# W681X.net
KiCad netlist of a schematic drawn in EAGLE
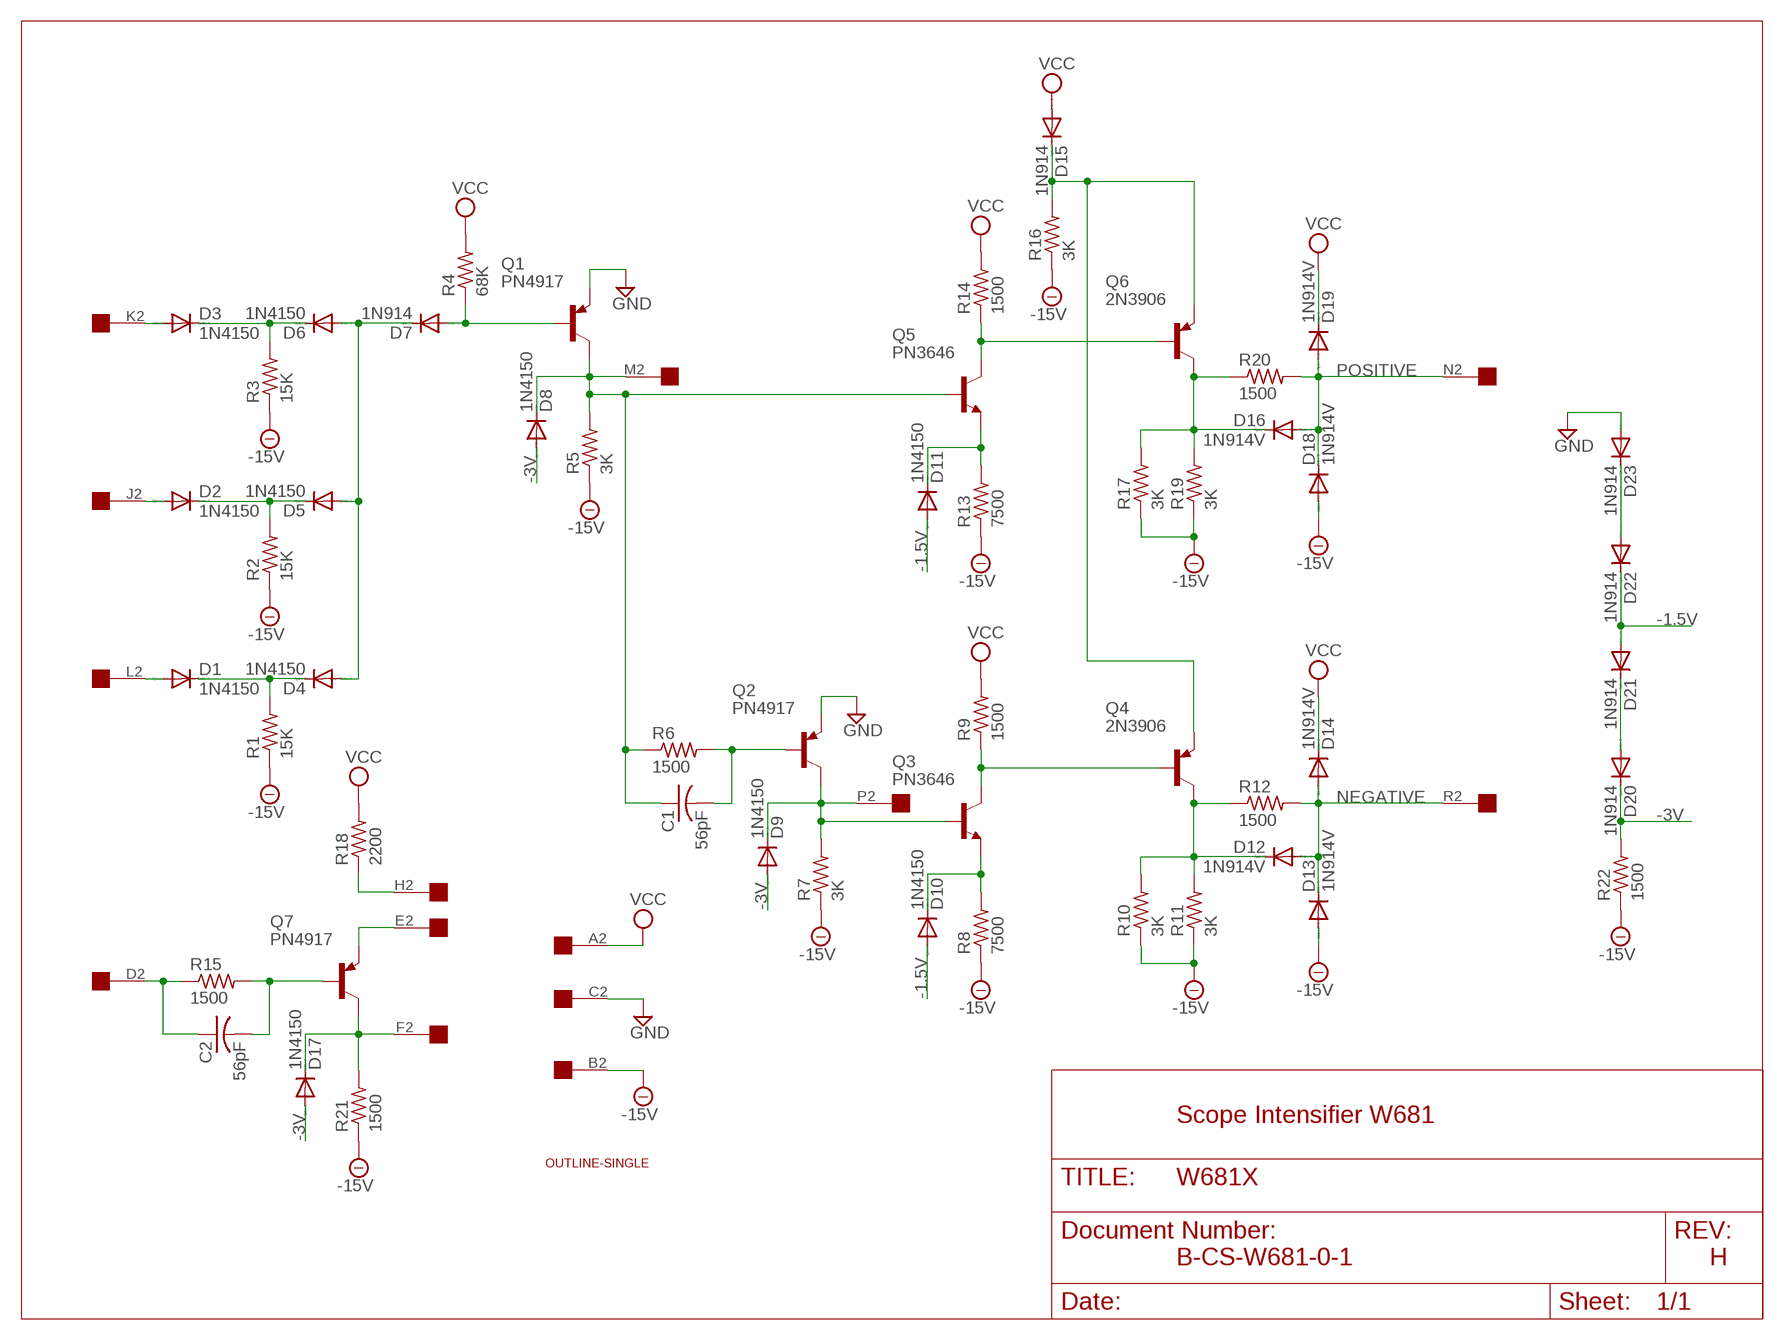
[diagram p0: schematic, sheet 1]

(export (version "E")
  (design (tool "Eeschema 10.0.6"))
  (components
    (comp (ref "C1")
      (value "56pF")
      (footprint "eagle-import:C063-025X075")
      (libsource (lib "eagle-import") (part "C-US"))
    )
    (comp (ref "C2")
      (value "56pF")
      (footprint "eagle-import:C063-025X075")
      (libsource (lib "eagle-import") (part "C-US"))
    )
    (comp (ref "D1")
      (value "1N4150")
      (footprint "eagle-import:DO35-10")
      (libsource (lib "eagle-import") (part "DIODE-DO35-10"))
    )
    (comp (ref "D2")
      (value "1N4150")
      (footprint "eagle-import:DO35-10")
      (libsource (lib "eagle-import") (part "DIODE-DO35-10"))
    )
    (comp (ref "D3")
      (value "1N4150")
      (footprint "eagle-import:DO35-10")
      (libsource (lib "eagle-import") (part "DIODE-DO35-10"))
    )
    (comp (ref "D4")
      (value "1N4150")
      (footprint "eagle-import:DO35-10")
      (libsource (lib "eagle-import") (part "DIODE-DO35-10"))
    )
    (comp (ref "D5")
      (value "1N4150")
      (footprint "eagle-import:DO35-10")
      (libsource (lib "eagle-import") (part "DIODE-DO35-10"))
    )
    (comp (ref "D6")
      (value "1N4150")
      (footprint "eagle-import:DO35-10")
      (libsource (lib "eagle-import") (part "DIODE-DO35-10"))
    )
    (comp (ref "D7")
      (value "1N914")
      (footprint "eagle-import:DO35-10")
      (libsource (lib "eagle-import") (part "DIODE-DO35-10"))
    )
    (comp (ref "D8")
      (value "1N4150")
      (footprint "eagle-import:DO35-10")
      (libsource (lib "eagle-import") (part "DIODE-DO35-10"))
    )
    (comp (ref "D9")
      (value "1N4150")
      (footprint "eagle-import:DO35-10")
      (libsource (lib "eagle-import") (part "DIODE-DO35-10"))
    )
    (comp (ref "D10")
      (value "1N4150")
      (footprint "eagle-import:DO35-10")
      (libsource (lib "eagle-import") (part "DIODE-DO35-10"))
    )
    (comp (ref "D11")
      (value "1N4150")
      (footprint "eagle-import:DO35-10")
      (libsource (lib "eagle-import") (part "DIODE-DO35-10"))
    )
    (comp (ref "D12")
      (value "1N914V")
      (footprint "eagle-import:DO35-10")
      (libsource (lib "eagle-import") (part "DIODE-DO35-10"))
    )
    (comp (ref "D13")
      (value "1N914V")
      (footprint "eagle-import:DO35-10")
      (libsource (lib "eagle-import") (part "DIODE-DO35-10"))
    )
    (comp (ref "D14")
      (value "1N914V")
      (footprint "eagle-import:DO35-10")
      (libsource (lib "eagle-import") (part "DIODE-DO35-10"))
    )
    (comp (ref "D15")
      (value "1N914")
      (footprint "eagle-import:DO35-10")
      (libsource (lib "eagle-import") (part "DIODE-DO35-10"))
    )
    (comp (ref "D16")
      (value "1N914V")
      (footprint "eagle-import:DO35-10")
      (libsource (lib "eagle-import") (part "DIODE-DO35-10"))
    )
    (comp (ref "D17")
      (value "1N4150")
      (footprint "eagle-import:DO35-10")
      (libsource (lib "eagle-import") (part "DIODE-DO35-10"))
    )
    (comp (ref "D18")
      (value "1N914V")
      (footprint "eagle-import:DO35-10")
      (libsource (lib "eagle-import") (part "DIODE-DO35-10"))
    )
    (comp (ref "D19")
      (value "1N914V")
      (footprint "eagle-import:DO35-10")
      (libsource (lib "eagle-import") (part "DIODE-DO35-10"))
    )
    (comp (ref "D20")
      (value "1N914")
      (footprint "eagle-import:DO35-10")
      (libsource (lib "eagle-import") (part "DIODE-DO35-10"))
    )
    (comp (ref "D21")
      (value "1N914")
      (footprint "eagle-import:DO35-10")
      (libsource (lib "eagle-import") (part "DIODE-DO35-10"))
    )
    (comp (ref "D22")
      (value "1N914")
      (footprint "eagle-import:DO35-10")
      (libsource (lib "eagle-import") (part "DIODE-DO35-10"))
    )
    (comp (ref "D23")
      (value "1N914")
      (footprint "eagle-import:DO35-10")
      (libsource (lib "eagle-import") (part "DIODE-DO35-10"))
    )
    (comp (ref "Q1")
      (value "PN4917")
      (footprint "eagle-import:TO5")
      (libsource (lib "eagle-import") (part "-PNP-TO5"))
    )
    (comp (ref "Q2")
      (value "PN4917")
      (footprint "eagle-import:TO5")
      (libsource (lib "eagle-import") (part "-PNP-TO5"))
    )
    (comp (ref "Q3")
      (value "PN3646")
      (footprint "eagle-import:TO5")
      (libsource (lib "eagle-import") (part "-NPN-TO5"))
    )
    (comp (ref "Q4")
      (value "2N3906")
      (footprint "eagle-import:TO5")
      (libsource (lib "eagle-import") (part "-PNP-TO5"))
    )
    (comp (ref "Q5")
      (value "PN3646")
      (footprint "eagle-import:TO5")
      (libsource (lib "eagle-import") (part "-NPN-TO5"))
    )
    (comp (ref "Q6")
      (value "2N3906")
      (footprint "eagle-import:TO5")
      (libsource (lib "eagle-import") (part "-PNP-TO5"))
    )
    (comp (ref "Q7")
      (value "PN4917")
      (footprint "eagle-import:TO5")
      (libsource (lib "eagle-import") (part "-PNP-TO5"))
    )
    (comp (ref "R1")
      (value "15K")
      (footprint "eagle-import:0207_10")
      (libsource (lib "eagle-import") (part "R-US_0207/10"))
    )
    (comp (ref "R2")
      (value "15K")
      (footprint "eagle-import:0207_10")
      (libsource (lib "eagle-import") (part "R-US_0207/10"))
    )
    (comp (ref "R3")
      (value "15K")
      (footprint "eagle-import:0207_10")
      (libsource (lib "eagle-import") (part "R-US_0207/10"))
    )
    (comp (ref "R4")
      (value "68K")
      (footprint "eagle-import:0207_10")
      (libsource (lib "eagle-import") (part "R-US_0207/10"))
    )
    (comp (ref "R5")
      (value "3K")
      (footprint "eagle-import:0207_10")
      (libsource (lib "eagle-import") (part "R-US_0207/10"))
    )
    (comp (ref "R6")
      (value "1500")
      (footprint "eagle-import:0207_10")
      (libsource (lib "eagle-import") (part "R-US_0207/10"))
    )
    (comp (ref "R7")
      (value "3K")
      (footprint "eagle-import:0207_10")
      (libsource (lib "eagle-import") (part "R-US_0207/10"))
    )
    (comp (ref "R8")
      (value "7500")
      (footprint "eagle-import:0207_10")
      (libsource (lib "eagle-import") (part "R-US_0207/10"))
    )
    (comp (ref "R9")
      (value "1500")
      (footprint "eagle-import:0207_10")
      (libsource (lib "eagle-import") (part "R-US_0207/10"))
    )
    (comp (ref "R10")
      (value "3K")
      (footprint "eagle-import:0207_10")
      (libsource (lib "eagle-import") (part "R-US_0207/10"))
    )
    (comp (ref "R11")
      (value "3K")
      (footprint "eagle-import:0207_10")
      (libsource (lib "eagle-import") (part "R-US_0207/10"))
    )
    (comp (ref "R12")
      (value "1500")
      (footprint "eagle-import:0207_10")
      (libsource (lib "eagle-import") (part "R-US_0207/10"))
    )
    (comp (ref "R13")
      (value "7500")
      (footprint "eagle-import:0207_10")
      (libsource (lib "eagle-import") (part "R-US_0207/10"))
    )
    (comp (ref "R14")
      (value "1500")
      (footprint "eagle-import:0207_10")
      (libsource (lib "eagle-import") (part "R-US_0207/10"))
    )
    (comp (ref "R15")
      (value "1500")
      (footprint "eagle-import:0207_10")
      (libsource (lib "eagle-import") (part "R-US_0207/10"))
    )
    (comp (ref "R16")
      (value "3K")
      (footprint "eagle-import:0207_10")
      (libsource (lib "eagle-import") (part "R-US_0207/10"))
    )
    (comp (ref "R17")
      (value "3K")
      (footprint "eagle-import:0207_10")
      (libsource (lib "eagle-import") (part "R-US_0207/10"))
    )
    (comp (ref "R18")
      (value "2200")
      (footprint "eagle-import:0207_10")
      (libsource (lib "eagle-import") (part "R-US_0207/10"))
    )
    (comp (ref "R19")
      (value "3K")
      (footprint "eagle-import:0207_10")
      (libsource (lib "eagle-import") (part "R-US_0207/10"))
    )
    (comp (ref "R20")
      (value "1500")
      (footprint "eagle-import:0207_10")
      (libsource (lib "eagle-import") (part "R-US_0207/10"))
    )
    (comp (ref "R21")
      (value "1500")
      (footprint "eagle-import:0207_10")
      (libsource (lib "eagle-import") (part "R-US_0207/10"))
    )
    (comp (ref "R22")
      (value "1500")
      (footprint "eagle-import:0207_10")
      (libsource (lib "eagle-import") (part "R-US_0207/10"))
    )
    (comp (ref "U$1")
      (value "OUTLINE-SINGLE")
      (footprint "eagle-import:SINGLE")
      (libsource (lib "eagle-import") (part "OUTLINE-SINGLE"))
    )
    (comp (ref "U$2")
      (value "EDGE-1")
      (footprint "eagle-import:EDGE-CON1")
      (libsource (lib "eagle-import") (part "EDGE-1"))
    )
  )
  (nets
    (net (code "1") (name "-15V") (class "Default")
      (node (ref "D13") (pin "A") (pinfunction "A_A") (pintype "passive"))
      (node (ref "D18") (pin "A") (pinfunction "A_A") (pintype "passive"))
      (node (ref "R1") (pin "1") (pinfunction "1_1") (pintype "passive"))
      (node (ref "R10") (pin "1") (pinfunction "1_1") (pintype "passive"))
      (node (ref "R11") (pin "1") (pinfunction "1_1") (pintype "passive"))
      (node (ref "R13") (pin "1") (pinfunction "1_1") (pintype "passive"))
      (node (ref "R16") (pin "1") (pinfunction "1_1") (pintype "passive"))
      (node (ref "R17") (pin "1") (pinfunction "1_1") (pintype "passive"))
      (node (ref "R19") (pin "1") (pinfunction "1_1") (pintype "passive"))
      (node (ref "R2") (pin "1") (pinfunction "1_1") (pintype "passive"))
      (node (ref "R21") (pin "1") (pinfunction "1_1") (pintype "passive"))
      (node (ref "R22") (pin "1") (pinfunction "1_1") (pintype "passive"))
      (node (ref "R3") (pin "1") (pinfunction "1_1") (pintype "passive"))
      (node (ref "R5") (pin "1") (pinfunction "1_1") (pintype "passive"))
      (node (ref "R7") (pin "1") (pinfunction "1_1") (pintype "passive"))
      (node (ref "R8") (pin "1") (pinfunction "1_1") (pintype "passive"))
      (node (ref "U$2") (pin "B2") (pinfunction "1_B2") (pintype "bidirectional"))
    )
    (net (code "2") (name "/-1.5V") (class "Default")
      (node (ref "D10") (pin "A") (pinfunction "A_A") (pintype "passive"))
      (node (ref "D11") (pin "A") (pinfunction "A_A") (pintype "passive"))
      (node (ref "D21") (pin "A") (pinfunction "A_A") (pintype "passive"))
      (node (ref "D22") (pin "C") (pinfunction "C_C") (pintype "passive"))
    )
    (net (code "3") (name "/-3V") (class "Default")
      (node (ref "D17") (pin "A") (pinfunction "A_A") (pintype "passive"))
      (node (ref "D20") (pin "C") (pinfunction "C_C") (pintype "passive"))
      (node (ref "D8") (pin "A") (pinfunction "A_A") (pintype "passive"))
      (node (ref "D9") (pin "A") (pinfunction "A_A") (pintype "passive"))
      (node (ref "R22") (pin "2") (pinfunction "2_2") (pintype "passive"))
    )
    (net (code "4") (name "/NEGATIVE") (class "Default")
      (node (ref "D12") (pin "A") (pinfunction "A_A") (pintype "passive"))
      (node (ref "D13") (pin "C") (pinfunction "C_C") (pintype "passive"))
      (node (ref "D14") (pin "A") (pinfunction "A_A") (pintype "passive"))
      (node (ref "R12") (pin "2") (pinfunction "2_2") (pintype "passive"))
      (node (ref "U$2") (pin "R2") (pinfunction "1_R2") (pintype "bidirectional"))
    )
    (net (code "5") (name "/POSITIVE") (class "Default")
      (node (ref "D16") (pin "A") (pinfunction "A_A") (pintype "passive"))
      (node (ref "D18") (pin "C") (pinfunction "C_C") (pintype "passive"))
      (node (ref "D19") (pin "A") (pinfunction "A_A") (pintype "passive"))
      (node (ref "R20") (pin "2") (pinfunction "2_2") (pintype "passive"))
      (node (ref "U$2") (pin "N2") (pinfunction "1_N2") (pintype "bidirectional"))
    )
    (net (code "6") (name "GND") (class "Default")
      (node (ref "D23") (pin "A") (pinfunction "A_A") (pintype "passive"))
      (node (ref "Q1") (pin "1") (pinfunction "E_1") (pintype "passive"))
      (node (ref "Q2") (pin "1") (pinfunction "E_1") (pintype "passive"))
      (node (ref "U$2") (pin "C2") (pinfunction "1_C2") (pintype "bidirectional"))
    )
    (net (code "7") (name "Net-(D1-PadC)") (class "Default")
      (node (ref "D1") (pin "C") (pinfunction "C_C") (pintype "passive"))
      (node (ref "D4") (pin "C") (pinfunction "C_C") (pintype "passive"))
      (node (ref "R1") (pin "2") (pinfunction "2_2") (pintype "passive"))
    )
    (net (code "8") (name "Net-(D2-PadC)") (class "Default")
      (node (ref "D2") (pin "C") (pinfunction "C_C") (pintype "passive"))
      (node (ref "D5") (pin "C") (pinfunction "C_C") (pintype "passive"))
      (node (ref "R2") (pin "2") (pinfunction "2_2") (pintype "passive"))
    )
    (net (code "9") (name "Net-(D3-PadC)") (class "Default")
      (node (ref "D3") (pin "C") (pinfunction "C_C") (pintype "passive"))
      (node (ref "D6") (pin "C") (pinfunction "C_C") (pintype "passive"))
      (node (ref "R3") (pin "2") (pinfunction "2_2") (pintype "passive"))
    )
    (net (code "10") (name "Net-(D4-PadA)") (class "Default")
      (node (ref "D4") (pin "A") (pinfunction "A_A") (pintype "passive"))
      (node (ref "D5") (pin "A") (pinfunction "A_A") (pintype "passive"))
      (node (ref "D6") (pin "A") (pinfunction "A_A") (pintype "passive"))
      (node (ref "D7") (pin "C") (pinfunction "C_C") (pintype "passive"))
    )
    (net (code "11") (name "Net-(D20-PadA)") (class "Default")
      (node (ref "D20") (pin "A") (pinfunction "A_A") (pintype "passive"))
      (node (ref "D21") (pin "C") (pinfunction "C_C") (pintype "passive"))
    )
    (net (code "12") (name "Net-(D22-PadA)") (class "Default")
      (node (ref "D22") (pin "A") (pinfunction "A_A") (pintype "passive"))
      (node (ref "D23") (pin "C") (pinfunction "C_C") (pintype "passive"))
    )
    (net (code "13") (name "Net-(Q1-B)") (class "Default")
      (node (ref "D7") (pin "A") (pinfunction "A_A") (pintype "passive"))
      (node (ref "Q1") (pin "2") (pinfunction "B_2") (pintype "passive"))
      (node (ref "R4") (pin "1") (pinfunction "1_1") (pintype "passive"))
    )
    (net (code "14") (name "Net-(Q1-C)") (class "Default")
      (node (ref "C1") (pin "1") (pinfunction "1_1") (pintype "passive"))
      (node (ref "D8") (pin "C") (pinfunction "C_C") (pintype "passive"))
      (node (ref "Q1") (pin "3") (pinfunction "C_3") (pintype "passive"))
      (node (ref "Q5") (pin "2") (pinfunction "B_2") (pintype "passive"))
      (node (ref "R5") (pin "2") (pinfunction "2_2") (pintype "passive"))
      (node (ref "R6") (pin "1") (pinfunction "1_1") (pintype "passive"))
      (node (ref "U$2") (pin "M2") (pinfunction "1_M2") (pintype "bidirectional"))
    )
    (net (code "15") (name "Net-(Q2-B)") (class "Default")
      (node (ref "C1") (pin "2") (pinfunction "2_2") (pintype "passive"))
      (node (ref "Q2") (pin "2") (pinfunction "B_2") (pintype "passive"))
      (node (ref "R6") (pin "2") (pinfunction "2_2") (pintype "passive"))
    )
    (net (code "16") (name "Net-(Q2-C)") (class "Default")
      (node (ref "D9") (pin "C") (pinfunction "C_C") (pintype "passive"))
      (node (ref "Q2") (pin "3") (pinfunction "C_3") (pintype "passive"))
      (node (ref "Q3") (pin "2") (pinfunction "B_2") (pintype "passive"))
      (node (ref "R7") (pin "2") (pinfunction "2_2") (pintype "passive"))
      (node (ref "U$2") (pin "P2") (pinfunction "1_P2") (pintype "bidirectional"))
    )
    (net (code "17") (name "Net-(Q3-C)") (class "Default")
      (node (ref "Q3") (pin "3") (pinfunction "C_3") (pintype "passive"))
      (node (ref "Q4") (pin "2") (pinfunction "B_2") (pintype "passive"))
      (node (ref "R9") (pin "1") (pinfunction "1_1") (pintype "passive"))
    )
    (net (code "18") (name "Net-(Q3-E)") (class "Default")
      (node (ref "D10") (pin "C") (pinfunction "C_C") (pintype "passive"))
      (node (ref "Q3") (pin "1") (pinfunction "E_1") (pintype "passive"))
      (node (ref "R8") (pin "2") (pinfunction "2_2") (pintype "passive"))
    )
    (net (code "19") (name "Net-(Q4-C)") (class "Default")
      (node (ref "D12") (pin "C") (pinfunction "C_C") (pintype "passive"))
      (node (ref "Q4") (pin "3") (pinfunction "C_3") (pintype "passive"))
      (node (ref "R10") (pin "2") (pinfunction "2_2") (pintype "passive"))
      (node (ref "R11") (pin "2") (pinfunction "2_2") (pintype "passive"))
      (node (ref "R12") (pin "1") (pinfunction "1_1") (pintype "passive"))
    )
    (net (code "20") (name "Net-(Q4-E)") (class "Default")
      (node (ref "D15") (pin "C") (pinfunction "C_C") (pintype "passive"))
      (node (ref "Q4") (pin "1") (pinfunction "E_1") (pintype "passive"))
      (node (ref "Q6") (pin "1") (pinfunction "E_1") (pintype "passive"))
      (node (ref "R16") (pin "2") (pinfunction "2_2") (pintype "passive"))
    )
    (net (code "21") (name "Net-(Q5-C)") (class "Default")
      (node (ref "Q5") (pin "3") (pinfunction "C_3") (pintype "passive"))
      (node (ref "Q6") (pin "2") (pinfunction "B_2") (pintype "passive"))
      (node (ref "R14") (pin "1") (pinfunction "1_1") (pintype "passive"))
    )
    (net (code "22") (name "Net-(Q5-E)") (class "Default")
      (node (ref "D11") (pin "C") (pinfunction "C_C") (pintype "passive"))
      (node (ref "Q5") (pin "1") (pinfunction "E_1") (pintype "passive"))
      (node (ref "R13") (pin "2") (pinfunction "2_2") (pintype "passive"))
    )
    (net (code "23") (name "Net-(Q6-C)") (class "Default")
      (node (ref "D16") (pin "C") (pinfunction "C_C") (pintype "passive"))
      (node (ref "Q6") (pin "3") (pinfunction "C_3") (pintype "passive"))
      (node (ref "R17") (pin "2") (pinfunction "2_2") (pintype "passive"))
      (node (ref "R19") (pin "2") (pinfunction "2_2") (pintype "passive"))
      (node (ref "R20") (pin "1") (pinfunction "1_1") (pintype "passive"))
    )
    (net (code "24") (name "Net-(Q7-B)") (class "Default")
      (node (ref "C2") (pin "2") (pinfunction "2_2") (pintype "passive"))
      (node (ref "Q7") (pin "2") (pinfunction "B_2") (pintype "passive"))
      (node (ref "R15") (pin "2") (pinfunction "2_2") (pintype "passive"))
    )
    (net (code "25") (name "Net-(Q7-C)") (class "Default")
      (node (ref "D17") (pin "C") (pinfunction "C_C") (pintype "passive"))
      (node (ref "Q7") (pin "3") (pinfunction "C_3") (pintype "passive"))
      (node (ref "R21") (pin "2") (pinfunction "2_2") (pintype "passive"))
      (node (ref "U$2") (pin "F2") (pinfunction "1_F2") (pintype "bidirectional"))
    )
    (net (code "26") (name "Net-(Q7-E)") (class "Default")
      (node (ref "Q7") (pin "1") (pinfunction "E_1") (pintype "passive"))
      (node (ref "U$2") (pin "E2") (pinfunction "1_E2") (pintype "bidirectional"))
    )
    (net (code "27") (name "Net-(U$2D-1)") (class "Default")
      (node (ref "C2") (pin "1") (pinfunction "1_1") (pintype "passive"))
      (node (ref "R15") (pin "1") (pinfunction "1_1") (pintype "passive"))
      (node (ref "U$2") (pin "D2") (pinfunction "1_D2") (pintype "bidirectional"))
    )
    (net (code "28") (name "Net-(U$2G-1)") (class "Default")
      (node (ref "R18") (pin "1") (pinfunction "1_1") (pintype "passive"))
      (node (ref "U$2") (pin "H2") (pinfunction "1_H2") (pintype "bidirectional"))
    )
    (net (code "29") (name "Net-(U$2H-1)") (class "Default")
      (node (ref "D2") (pin "A") (pinfunction "A_A") (pintype "passive"))
      (node (ref "U$2") (pin "J2") (pinfunction "1_J2") (pintype "bidirectional"))
    )
    (net (code "30") (name "Net-(U$2I-1)") (class "Default")
      (node (ref "D3") (pin "A") (pinfunction "A_A") (pintype "passive"))
      (node (ref "U$2") (pin "K2") (pinfunction "1_K2") (pintype "bidirectional"))
    )
    (net (code "31") (name "Net-(U$2J-1)") (class "Default")
      (node (ref "D1") (pin "A") (pinfunction "A_A") (pintype "passive"))
      (node (ref "U$2") (pin "L2") (pinfunction "1_L2") (pintype "bidirectional"))
    )
    (net (code "32") (name "VCC") (class "Default")
      (node (ref "D14") (pin "C") (pinfunction "C_C") (pintype "passive"))
      (node (ref "D15") (pin "A") (pinfunction "A_A") (pintype "passive"))
      (node (ref "D19") (pin "C") (pinfunction "C_C") (pintype "passive"))
      (node (ref "R14") (pin "2") (pinfunction "2_2") (pintype "passive"))
      (node (ref "R18") (pin "2") (pinfunction "2_2") (pintype "passive"))
      (node (ref "R4") (pin "2") (pinfunction "2_2") (pintype "passive"))
      (node (ref "R9") (pin "2") (pinfunction "2_2") (pintype "passive"))
      (node (ref "U$2") (pin "A2") (pinfunction "1_A2") (pintype "bidirectional"))
    )
  )
)
